# FPGA_misc.net
KiCad netlist of a schematic drawn in Altium Designer
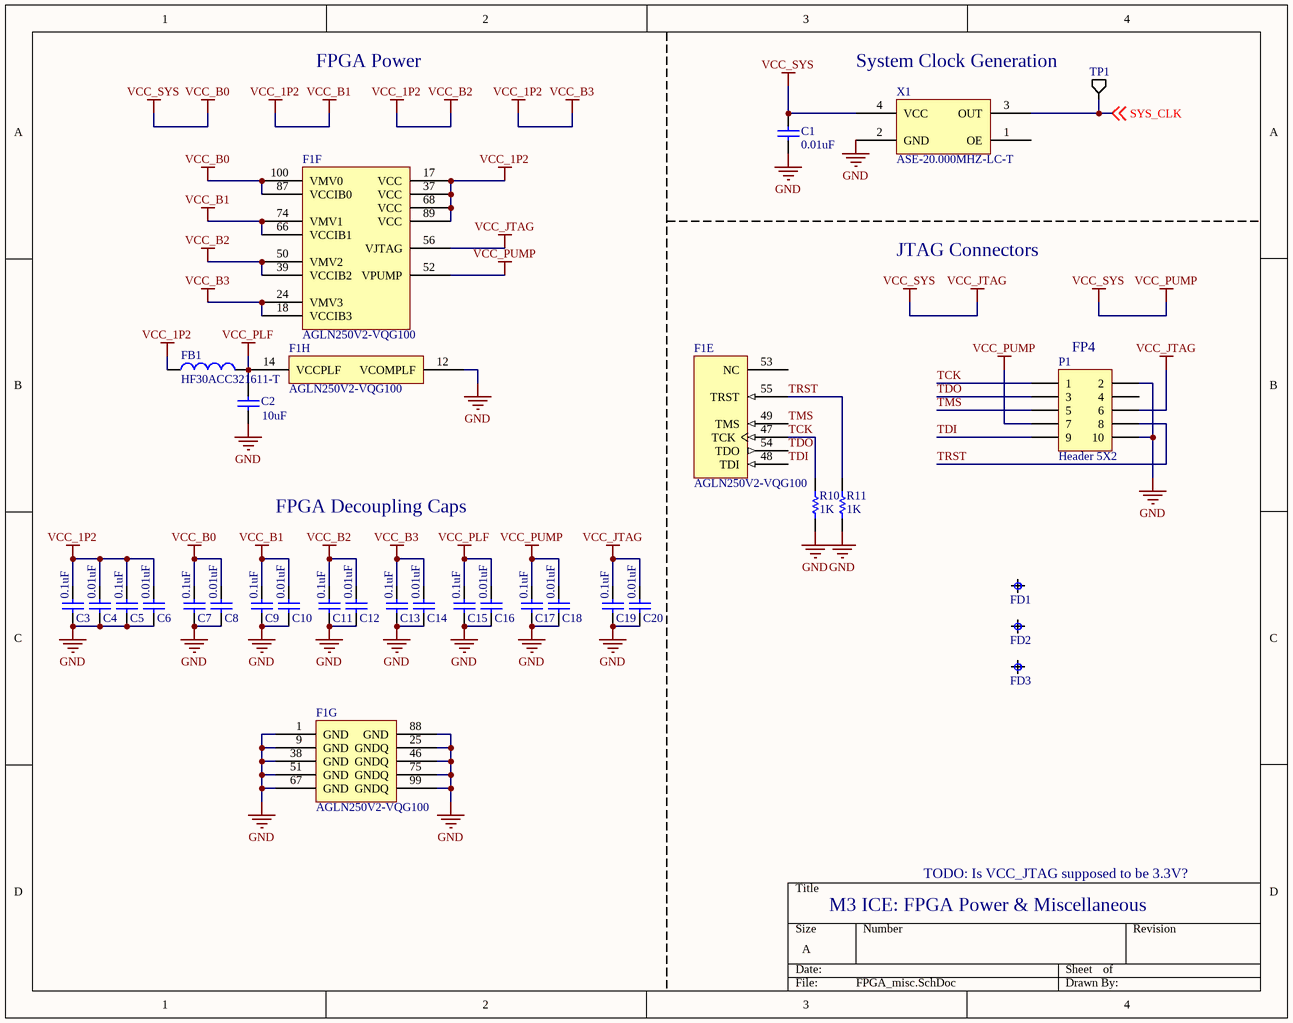
[diagram p0: FPGA_misc.SchDoc]

(export (version "E")
  (design (tool "Eeschema 10.0.6"))
  (components
    (comp (ref "C1")
      (value "0.01uF")
      (footprint "1608[0603]")
      (description "Capacitor (Semiconductor SIM Model)")
      (fields
        (field (name "DISTPARTNO") "445-1311-1-ND")
        (field (name "MANPARTNO") "C1608X7R1H103K")
        (field (name "PUBLISHER") "Altium Limited")
      )
      (libsource (lib "Miscellaneous Devices") (part "Cap Semi"))
    )
    (comp (ref "C2")
      (value "10uF")
      (footprint "0805")
      (description "Capacitor (Semiconductor SIM Model)")
      (fields
        (field (name "DISTPARTNO") "445-6857-1-ND")
        (field (name "MANPARTNO") "C2012X7R1A106K")
        (field (name "PUBLISHER") "Altium Limited")
      )
      (libsource (lib "M3") (part "Cap Chip"))
    )
    (comp (ref "C3")
      (value "0.1uF")
      (footprint "1608[0603]")
      (description "Capacitor (Semiconductor SIM Model)")
      (fields
        (field (name "DISTPARTNO") "1276-1005-1-ND")
        (field (name "MANPARTNO") "CL10B104KO8NNNC")
        (field (name "PUBLISHER") "Altium Limited")
      )
      (libsource (lib "Miscellaneous Devices") (part "Cap Semi"))
    )
    (comp (ref "C4")
      (value "0.01uF")
      (footprint "1608[0603]")
      (description "Capacitor (Semiconductor SIM Model)")
      (fields
        (field (name "DISTPARTNO") "445-1311-1-ND")
        (field (name "MANPARTNO") "C1608X7R1H103K")
        (field (name "PUBLISHER") "Altium Limited")
      )
      (libsource (lib "Miscellaneous Devices") (part "Cap Semi"))
    )
    (comp (ref "C5")
      (value "0.1uF")
      (footprint "1608[0603]")
      (description "Capacitor (Semiconductor SIM Model)")
      (fields
        (field (name "DISTPARTNO") "1276-1005-1-ND")
        (field (name "MANPARTNO") "CL10B104KO8NNNC")
        (field (name "PUBLISHER") "Altium Limited")
      )
      (libsource (lib "Miscellaneous Devices") (part "Cap Semi"))
    )
    (comp (ref "C6")
      (value "0.01uF")
      (footprint "1608[0603]")
      (description "Capacitor (Semiconductor SIM Model)")
      (fields
        (field (name "DISTPARTNO") "445-1311-1-ND")
        (field (name "MANPARTNO") "C1608X7R1H103K")
        (field (name "PUBLISHER") "Altium Limited")
      )
      (libsource (lib "Miscellaneous Devices") (part "Cap Semi"))
    )
    (comp (ref "C7")
      (value "0.1uF")
      (footprint "1608[0603]")
      (description "Capacitor (Semiconductor SIM Model)")
      (fields
        (field (name "DISTPARTNO") "1276-1005-1-ND")
        (field (name "MANPARTNO") "CL10B104KO8NNNC")
        (field (name "PUBLISHER") "Altium Limited")
      )
      (libsource (lib "Miscellaneous Devices") (part "Cap Semi"))
    )
    (comp (ref "C8")
      (value "0.01uF")
      (footprint "1608[0603]")
      (description "Capacitor (Semiconductor SIM Model)")
      (fields
        (field (name "DISTPARTNO") "445-1311-1-ND")
        (field (name "MANPARTNO") "C1608X7R1H103K")
        (field (name "PUBLISHER") "Altium Limited")
      )
      (libsource (lib "Miscellaneous Devices") (part "Cap Semi"))
    )
    (comp (ref "C9")
      (value "0.1uF")
      (footprint "1608[0603]")
      (description "Capacitor (Semiconductor SIM Model)")
      (fields
        (field (name "DISTPARTNO") "1276-1005-1-ND")
        (field (name "MANPARTNO") "CL10B104KO8NNNC")
        (field (name "PUBLISHER") "Altium Limited")
      )
      (libsource (lib "Miscellaneous Devices") (part "Cap Semi"))
    )
    (comp (ref "C10")
      (value "0.01uF")
      (footprint "1608[0603]")
      (description "Capacitor (Semiconductor SIM Model)")
      (fields
        (field (name "DISTPARTNO") "445-1311-1-ND")
        (field (name "MANPARTNO") "C1608X7R1H103K")
        (field (name "PUBLISHER") "Altium Limited")
      )
      (libsource (lib "Miscellaneous Devices") (part "Cap Semi"))
    )
    (comp (ref "C11")
      (value "0.1uF")
      (footprint "1608[0603]")
      (description "Capacitor (Semiconductor SIM Model)")
      (fields
        (field (name "DISTPARTNO") "1276-1005-1-ND")
        (field (name "MANPARTNO") "CL10B104KO8NNNC")
        (field (name "PUBLISHER") "Altium Limited")
      )
      (libsource (lib "Miscellaneous Devices") (part "Cap Semi"))
    )
    (comp (ref "C12")
      (value "0.01uF")
      (footprint "1608[0603]")
      (description "Capacitor (Semiconductor SIM Model)")
      (fields
        (field (name "DISTPARTNO") "445-1311-1-ND")
        (field (name "MANPARTNO") "C1608X7R1H103K")
        (field (name "PUBLISHER") "Altium Limited")
      )
      (libsource (lib "Miscellaneous Devices") (part "Cap Semi"))
    )
    (comp (ref "C13")
      (value "0.1uF")
      (footprint "1608[0603]")
      (description "Capacitor (Semiconductor SIM Model)")
      (fields
        (field (name "DISTPARTNO") "1276-1005-1-ND")
        (field (name "MANPARTNO") "CL10B104KO8NNNC")
        (field (name "PUBLISHER") "Altium Limited")
      )
      (libsource (lib "Miscellaneous Devices") (part "Cap Semi"))
    )
    (comp (ref "C14")
      (value "0.01uF")
      (footprint "1608[0603]")
      (description "Capacitor (Semiconductor SIM Model)")
      (fields
        (field (name "DISTPARTNO") "445-1311-1-ND")
        (field (name "MANPARTNO") "C1608X7R1H103K")
        (field (name "PUBLISHER") "Altium Limited")
      )
      (libsource (lib "Miscellaneous Devices") (part "Cap Semi"))
    )
    (comp (ref "C15")
      (value "0.1uF")
      (footprint "1608[0603]")
      (description "Capacitor (Semiconductor SIM Model)")
      (fields
        (field (name "DISTPARTNO") "1276-1005-1-ND")
        (field (name "MANPARTNO") "CL10B104KO8NNNC")
        (field (name "PUBLISHER") "Altium Limited")
      )
      (libsource (lib "Miscellaneous Devices") (part "Cap Semi"))
    )
    (comp (ref "C16")
      (value "0.01uF")
      (footprint "1608[0603]")
      (description "Capacitor (Semiconductor SIM Model)")
      (fields
        (field (name "DISTPARTNO") "445-1311-1-ND")
        (field (name "MANPARTNO") "C1608X7R1H103K")
        (field (name "PUBLISHER") "Altium Limited")
      )
      (libsource (lib "Miscellaneous Devices") (part "Cap Semi"))
    )
    (comp (ref "C17")
      (value "0.1uF")
      (footprint "1608[0603]")
      (description "Capacitor (Semiconductor SIM Model)")
      (fields
        (field (name "DISTPARTNO") "1276-1005-1-ND")
        (field (name "MANPARTNO") "CL10B104KO8NNNC")
        (field (name "PUBLISHER") "Altium Limited")
      )
      (libsource (lib "Miscellaneous Devices") (part "Cap Semi"))
    )
    (comp (ref "C18")
      (value "0.01uF")
      (footprint "1608[0603]")
      (description "Capacitor (Semiconductor SIM Model)")
      (fields
        (field (name "DISTPARTNO") "445-1311-1-ND")
        (field (name "MANPARTNO") "C1608X7R1H103K")
        (field (name "PUBLISHER") "Altium Limited")
      )
      (libsource (lib "Miscellaneous Devices") (part "Cap Semi"))
    )
    (comp (ref "C19")
      (value "0.1uF")
      (footprint "1608[0603]")
      (description "Capacitor (Semiconductor SIM Model)")
      (fields
        (field (name "DISTPARTNO") "1276-1005-1-ND")
        (field (name "MANPARTNO") "CL10B104KO8NNNC")
        (field (name "PUBLISHER") "Altium Limited")
      )
      (libsource (lib "Miscellaneous Devices") (part "Cap Semi"))
    )
    (comp (ref "C20")
      (value "0.01uF")
      (footprint "1608[0603]")
      (description "Capacitor (Semiconductor SIM Model)")
      (fields
        (field (name "DISTPARTNO") "445-1311-1-ND")
        (field (name "MANPARTNO") "C1608X7R1H103K")
        (field (name "PUBLISHER") "Altium Limited")
      )
      (libsource (lib "Miscellaneous Devices") (part "Cap Semi"))
    )
    (comp (ref "F1")
      (value "AGLN250V2-VQG100")
      (footprint "VQ100_N")
      (fields (field (name "DISTPARTNO") "1100-1134-ND") (field (name "PUBLISHER") "Altium Limited"))
      (libsource (lib "Actel IGLOO nano") (part "AGLN250V2-VQG100"))
    )
    (comp (ref "FB1")
      (value "HF30ACC321611-T")
      (footprint "Ferrite_Bead_3.2mm_1.6mm")
      (fields (field (name "DISTPARTNO") "445-6165-1-ND"))
      (libsource (lib "M3") (part "Ferrite Bead HF30ACC321611-T"))
    )
    (comp (ref "FD1")
      (value "FIDUCIAL")
      (footprint "FIDUCIAL")
      (libsource (lib "uwb-library") (part "FIDUCIAL"))
    )
    (comp (ref "FD2")
      (value "FIDUCIAL")
      (footprint "FIDUCIAL")
      (libsource (lib "uwb-library") (part "FIDUCIAL"))
    )
    (comp (ref "FD3")
      (value "FIDUCIAL")
      (footprint "FIDUCIAL")
      (libsource (lib "uwb-library") (part "FIDUCIAL"))
    )
    (comp (ref "P1")
      (value "Header 5X2")
      (footprint "HDR2X5")
      (description "Header, 5-Pin, Dual row")
      (fields
        (field (name "DISTPARTNO") "A26530-05-ND")
        (field (name "MANPARTNO") "4-103328-0-05")
        (field (name "PUBLISHER") "Altium Limited")
      )
      (libsource (lib "Miscellaneous Connectors") (part "Header 5X2"))
    )
    (comp (ref "R10")
      (value "1K")
      (footprint "0603")
      (description "Semiconductor Resistor")
      (fields
        (field (name "DISTPARTNO") "P1.0KGCT-ND")
        (field (name "MANPARTNO") "ERJ-3GEYJ102V")
        (field (name "PUBLISHER") "Altium Limited")
      )
      (libsource (lib "M3") (part "Res Chip"))
    )
    (comp (ref "R11")
      (value "1K")
      (footprint "0603")
      (description "Semiconductor Resistor")
      (fields
        (field (name "DISTPARTNO") "P1.0KGCT-ND")
        (field (name "MANPARTNO") "ERJ-3GEYJ102V")
        (field (name "PUBLISHER") "Altium Limited")
      )
      (libsource (lib "M3") (part "Res Chip"))
    )
    (comp (ref "TP1") (value "TP") (footprint "TP") (libsource (lib "M3") (part "TP")))
    (comp (ref "X1")
      (value "ASE-20.000MHZ-LC-T")
      (footprint "CRYSTAL_3.2mm_2.5mm")
      (fields (field (name "DISTPARTNO") "535-9565-1-ND"))
      (libsource (lib "M3") (part "ASE-20.000MHZ-LC-T"))
    )
  )
  (nets
    (net (code "1") (name "/TCK") (class "Default")
      (node (ref "F1") (pin "47") (pinfunction "TCK_47") (pintype "input"))
      (node (ref "P1") (pin "1") (pinfunction "1_1") (pintype "passive"))
      (node (ref "R10") (pin "1") (pinfunction "1_1") (pintype "passive"))
    )
    (net (code "2") (name "/TDI") (class "Default")
      (node (ref "F1") (pin "48") (pinfunction "TDI_48") (pintype "input"))
      (node (ref "P1") (pin "9") (pinfunction "9_9") (pintype "passive"))
    )
    (net (code "3") (name "/TDO") (class "Default")
      (node (ref "F1") (pin "54") (pinfunction "TDO_54") (pintype "output"))
      (node (ref "P1") (pin "3") (pinfunction "3_3") (pintype "passive"))
    )
    (net (code "4") (name "/TMS") (class "Default")
      (node (ref "F1") (pin "49") (pinfunction "TMS_49") (pintype "input"))
      (node (ref "P1") (pin "5") (pinfunction "5_5") (pintype "passive"))
    )
    (net (code "5") (name "/TRST") (class "Default")
      (node (ref "F1") (pin "55") (pinfunction "TRST_55") (pintype "input"))
      (node (ref "P1") (pin "8") (pinfunction "8_8") (pintype "passive"))
      (node (ref "R11") (pin "1") (pinfunction "1_1") (pintype "passive"))
    )
    (net (code "6") (name "GND") (class "Default")
      (node (ref "C1") (pin "1") (pinfunction "1_1") (pintype "passive"))
      (node (ref "C10") (pin "1") (pinfunction "1_1") (pintype "passive"))
      (node (ref "C11") (pin "1") (pinfunction "1_1") (pintype "passive"))
      (node (ref "C12") (pin "1") (pinfunction "1_1") (pintype "passive"))
      (node (ref "C13") (pin "1") (pinfunction "1_1") (pintype "passive"))
      (node (ref "C14") (pin "1") (pinfunction "1_1") (pintype "passive"))
      (node (ref "C15") (pin "1") (pinfunction "1_1") (pintype "passive"))
      (node (ref "C16") (pin "1") (pinfunction "1_1") (pintype "passive"))
      (node (ref "C17") (pin "1") (pinfunction "1_1") (pintype "passive"))
      (node (ref "C18") (pin "1") (pinfunction "1_1") (pintype "passive"))
      (node (ref "C19") (pin "1") (pinfunction "1_1") (pintype "passive"))
      (node (ref "C2") (pin "1") (pinfunction "1_1") (pintype "passive"))
      (node (ref "C20") (pin "1") (pinfunction "1_1") (pintype "passive"))
      (node (ref "C3") (pin "1") (pinfunction "1_1") (pintype "passive"))
      (node (ref "C4") (pin "1") (pinfunction "1_1") (pintype "passive"))
      (node (ref "C5") (pin "1") (pinfunction "1_1") (pintype "passive"))
      (node (ref "C6") (pin "1") (pinfunction "1_1") (pintype "passive"))
      (node (ref "C7") (pin "1") (pinfunction "1_1") (pintype "passive"))
      (node (ref "C8") (pin "1") (pinfunction "1_1") (pintype "passive"))
      (node (ref "C9") (pin "1") (pinfunction "1_1") (pintype "passive"))
      (node (ref "F1") (pin "1") (pinfunction "GND_1") (pintype "power_in"))
      (node (ref "F1") (pin "12") (pinfunction "VCOMPLF_12") (pintype "power_in"))
      (node (ref "F1") (pin "25") (pinfunction "GNDQ_25") (pintype "power_in"))
      (node (ref "F1") (pin "38") (pinfunction "GND_38") (pintype "power_in"))
      (node (ref "F1") (pin "46") (pinfunction "GNDQ_46") (pintype "power_in"))
      (node (ref "F1") (pin "51") (pinfunction "GND_51") (pintype "power_in"))
      (node (ref "F1") (pin "67") (pinfunction "GND_67") (pintype "power_in"))
      (node (ref "F1") (pin "75") (pinfunction "GNDQ_75") (pintype "power_in"))
      (node (ref "F1") (pin "88") (pinfunction "GND_88") (pintype "power_in"))
      (node (ref "F1") (pin "9") (pinfunction "GND_9") (pintype "power_in"))
      (node (ref "F1") (pin "99") (pinfunction "GNDQ_99") (pintype "power_in"))
      (node (ref "P1") (pin "10") (pinfunction "10_10") (pintype "passive"))
      (node (ref "P1") (pin "2") (pinfunction "2_2") (pintype "passive"))
      (node (ref "R10") (pin "2") (pinfunction "2_2") (pintype "passive"))
      (node (ref "R11") (pin "2") (pinfunction "2_2") (pintype "passive"))
      (node (ref "X1") (pin "2") (pinfunction "GND_2") (pintype "passive"))
    )
    (net (code "7") (name "SYS_CLK") (class "Default")
      (node (ref "TP1") (pin "1") (pinfunction "A_1") (pintype "passive"))
      (node (ref "X1") (pin "3") (pinfunction "OUT_3") (pintype "passive"))
    )
    (net (code "8") (name "VCC_1P2") (class "Default")
      (node (ref "C10") (pin "2") (pinfunction "2_2") (pintype "passive"))
      (node (ref "C11") (pin "2") (pinfunction "2_2") (pintype "passive"))
      (node (ref "C12") (pin "2") (pinfunction "2_2") (pintype "passive"))
      (node (ref "C13") (pin "2") (pinfunction "2_2") (pintype "passive"))
      (node (ref "C14") (pin "2") (pinfunction "2_2") (pintype "passive"))
      (node (ref "C3") (pin "2") (pinfunction "2_2") (pintype "passive"))
      (node (ref "C4") (pin "2") (pinfunction "2_2") (pintype "passive"))
      (node (ref "C5") (pin "2") (pinfunction "2_2") (pintype "passive"))
      (node (ref "C6") (pin "2") (pinfunction "2_2") (pintype "passive"))
      (node (ref "C9") (pin "2") (pinfunction "2_2") (pintype "passive"))
      (node (ref "F1") (pin "17") (pinfunction "VCC_17") (pintype "power_in"))
      (node (ref "F1") (pin "18") (pinfunction "VCCIB3_18") (pintype "power_in"))
      (node (ref "F1") (pin "24") (pinfunction "VMV3_24") (pintype "power_in"))
      (node (ref "F1") (pin "37") (pinfunction "VCC_37") (pintype "power_in"))
      (node (ref "F1") (pin "39") (pinfunction "VCCIB2_39") (pintype "power_in"))
      (node (ref "F1") (pin "50") (pinfunction "VMV2_50") (pintype "power_in"))
      (node (ref "F1") (pin "66") (pinfunction "VCCIB1_66") (pintype "power_in"))
      (node (ref "F1") (pin "68") (pinfunction "VCC_68") (pintype "power_in"))
      (node (ref "F1") (pin "74") (pinfunction "VMV1_74") (pintype "power_in"))
      (node (ref "F1") (pin "89") (pinfunction "VCC_89") (pintype "power_in"))
      (node (ref "FB1") (pin "1") (pinfunction "1_1") (pintype "passive"))
    )
    (net (code "9") (name "VCC_B0") (class "Default")
      (node (ref "C1") (pin "2") (pinfunction "2_2") (pintype "passive"))
      (node (ref "C17") (pin "2") (pinfunction "2_2") (pintype "passive"))
      (node (ref "C18") (pin "2") (pinfunction "2_2") (pintype "passive"))
      (node (ref "C19") (pin "2") (pinfunction "2_2") (pintype "passive"))
      (node (ref "C20") (pin "2") (pinfunction "2_2") (pintype "passive"))
      (node (ref "C7") (pin "2") (pinfunction "2_2") (pintype "passive"))
      (node (ref "C8") (pin "2") (pinfunction "2_2") (pintype "passive"))
      (node (ref "F1") (pin "100") (pinfunction "VMV0_100") (pintype "power_in"))
      (node (ref "F1") (pin "52") (pinfunction "VPUMP_52") (pintype "power_in"))
      (node (ref "F1") (pin "56") (pinfunction "VJTAG_56") (pintype "power_in"))
      (node (ref "F1") (pin "87") (pinfunction "VCCIB0_87") (pintype "power_in"))
      (node (ref "P1") (pin "6") (pinfunction "6_6") (pintype "passive"))
      (node (ref "P1") (pin "7") (pinfunction "7_7") (pintype "passive"))
      (node (ref "X1") (pin "4") (pinfunction "VCC_4") (pintype "passive"))
    )
    (net (code "10") (name "VCC_PLF") (class "Default")
      (node (ref "C15") (pin "2") (pinfunction "2_2") (pintype "passive"))
      (node (ref "C16") (pin "2") (pinfunction "2_2") (pintype "passive"))
      (node (ref "C2") (pin "2") (pinfunction "2_2") (pintype "passive"))
      (node (ref "F1") (pin "14") (pinfunction "VCCPLF_14") (pintype "power_in"))
      (node (ref "FB1") (pin "2") (pinfunction "2_2") (pintype "passive"))
    )
    (net (code "11") (name "unconnected-(F1E-NC-Pad53)") (class "Default")
      (node (ref "F1") (pin "53") (pinfunction "NC_53") (pintype "passive"))
    )
    (net (code "12") (name "unconnected-(P1-Pad4)") (class "Default")
      (node (ref "P1") (pin "4") (pinfunction "4_4") (pintype "passive"))
    )
    (net (code "13") (name "unconnected-(X1-OE-Pad1)") (class "Default")
      (node (ref "X1") (pin "1") (pinfunction "OE_1") (pintype "passive"))
    )
  )
)
